# Test.net
KiCad netlist of a schematic drawn in Altium Designer
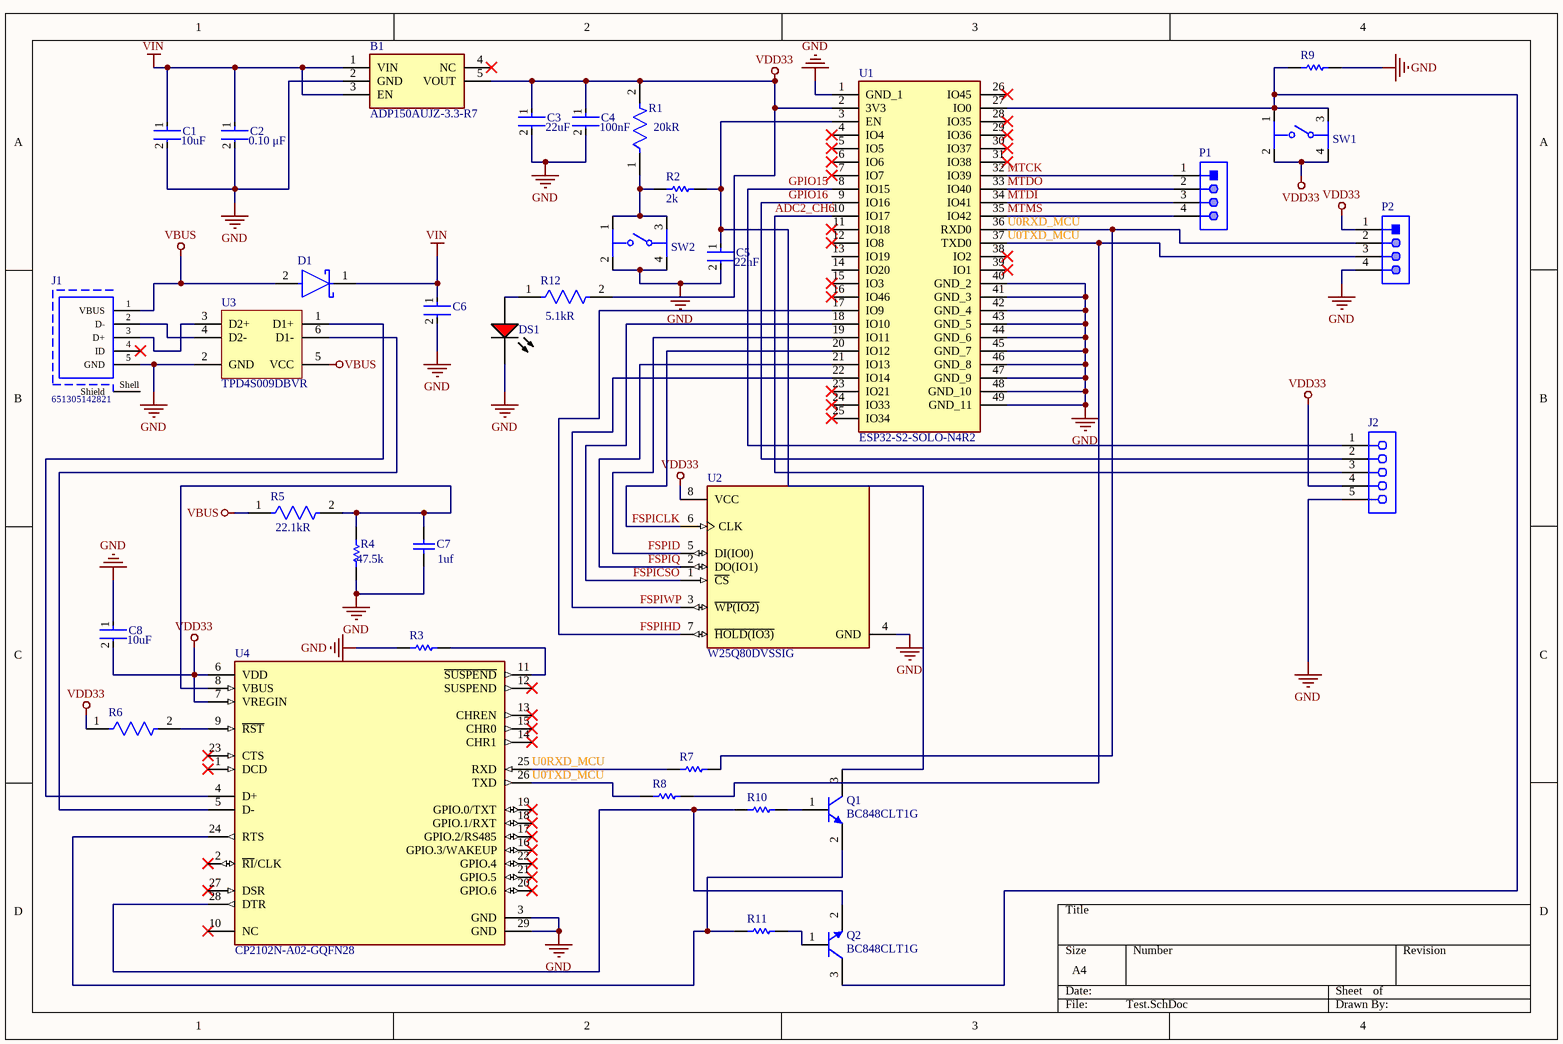
[diagram p0: Test.SchDoc]

(export (version "E")
  (design (tool "Eeschema 10.0.6"))
  (components
    (comp (ref "B1")
      (value "ADP150AUJZ-3.3-R7")
      (footprint "SOT95P280X100-5N")
      (description "Ultralow Noise, 150 mA CMOS Linear Regulator")
      (libsource (lib "Integrated_Library1") (part "ADP150AUJZ-3.3-R7"))
    )
    (comp (ref "C1")
      (value "GRM21BR61C106KE15L")
      (footprint "FP-GRM21B-0_1-IPC_C")
      (description "Chip Multilayer Ceramic Capacitors for General Purpose, 0805, 10uF, X5R, 15%, 10%, 16V")
      (fields
        (field (name "TOLERANCE") "10%")
        (field (name "VOLTAGE") "16V")
        (field (name "CAPACITANCE") "10uF")
      )
      (libsource (lib "Altium Content Vault") (part "b4654b650e69147ec39a6b967a45e02"))
    )
    (comp (ref "C2")
      (value "C1206C104K1RACTU")
      (footprint "FP-C1206C-EB-MFG")
      (description "CAP CER 0.1UF 100V X7R 1206")
      (fields
        (field (name "TOLERANCE") "0.1")
        (field (name "OCTOPART") "https://octopart.com/c1206c104k1ractu-kemet-89521")
        (field (name "CAPACITANCE") "0.10 μF")
      )
      (libsource (lib "Altium Content Vault") (part "b4654b650e69147ec39a6b967a45e02"))
    )
    (comp (ref "C3")
      (value "GRM21BR60J226ME39L")
      (footprint "FP-GRM21B-0_15-MFG")
      (description "Chip Multilayer Ceramic Capacitors for General Purpose, 0805, 22uF, X5R, 15%, 20%, 6.3V")
      (fields
        (field (name "VOLTAGE") "6.3V")
        (field (name "TOLERANCE") "20%")
        (field (name "CAPACITANCE") "22uF")
      )
      (libsource (lib "Altium Content Vault") (part "b4654b650e69147ec39a6b967a45e02"))
    )
    (comp (ref "C4")
      (value "CL03A104KQ3NNNH")
      (footprint "FP-CL03-IPC_B")
      (description "Cap Ceramic 100nF 6.3V X5R ±10% Pad SMD 0201 +85°C T/R")
      (fields (field (name "TOLERANCE") "10%") (field (name "CAPACITANCE") "100nF"))
      (libsource (lib "Altium Content Vault") (part "b4654b650e69147ec39a6b967a45e02"))
    )
    (comp (ref "C5")
      (value "CL21B223KBANNNC")
      (footprint "FP-CL21-IPC_A")
      (description "CL21 Series 0805 22nF 50V ±10% Tolerance X7R Multilayer Ceramic Chip Capacitor")
      (fields
        (field (name "TOLERANCE") "10%")
        (field (name "VOLTAGE") "50V")
        (field (name "CAPACITANCE") "22nF")
      )
      (libsource (lib "Altium Content Vault") (part "b4654b650e69147ec39a6b967a45e02"))
    )
    (comp (ref "C6")
      (value "GRM21BR61E106KA73L")
      (footprint "FP-GRM21B-0_15-IPC_C")
      (description "Chip Multilayer Ceramic Capacitors for General Purpose, 0805, 10uF, X5R, 15%, 10%, 25V")
      (fields (field (name "VOLTAGE") "25V") (field (name "TOLERANCE") "10%"))
      (libsource (lib "Altium Content Vault") (part "b4654b650e69147ec39a6b967a45e02"))
    )
    (comp (ref "C7")
      (value "1uf")
      (footprint "CAPC2013X145X50LL20T25")
      (fields (field (name "MANUFACTURER") "Kemet") (field (name "PART NUMBER") "C0805C105K4PACTU"))
      (libsource (lib "Altium Content Vault") (part "CAP"))
    )
    (comp (ref "C8")
      (value "GRM21BR61C106KE15L")
      (footprint "FP-GRM21B-0_1-IPC_C")
      (description "Chip Multilayer Ceramic Capacitors for General Purpose, 0805, 10uF, X5R, 15%, 10%, 16V")
      (fields
        (field (name "TOLERANCE") "10%")
        (field (name "VOLTAGE") "16V")
        (field (name "CAPACITANCE") "10uF")
      )
      (libsource (lib "Altium Content Vault") (part "b4654b650e69147ec39a6b967a45e02"))
    )
    (comp (ref "D1")
      (value "MSS1P4-M3/89A")
      (footprint "FP-96591-MFG")
      (description "DIODE SCHOTTKY 40V 1A MICROSMP")
      (fields
        (field (name "OCTOPART") "https://octopart.com/mss1p4-m3%2F89a-vishay-42505723")
        (field (name "MANUFACTURER") "Vishay")
      )
      (libsource (lib "Altium Content Vault") (part "c1678fac7984e62e0809fbf79c06691"))
    )
    (comp (ref "DS1")
      (value "TLMS1100-GS08")
      (footprint "VISH-TLMX1100_V")
      (description "LED, RED, 2.1 V, -40 to 100 degC, 2-Pin SMD (0603), RoHS, Tape and Reel")
      (fields (field (name "TOLERANCE") "5%"))
      (libsource (lib "Altium Content Vault") (part "LED-RED-AK-2"))
    )
    (comp (ref "J1")
      (value "651305142821")
      (footprint "651305142821")
      (description "Mini USB 2.0 Type AB Receptacle WR-COM, Horizontal, SMT, with Pads")
      (fields (field (name "MANUFACTURER") "Wurth Elektronik") (field (name "PUBLISHER") "WurthElektronik"))
      (libsource (lib "Altium Content Vault") (part "WE-USB-5-1SHLD"))
    )
    (comp (ref "J2")
      (value "SSW-105-01-G-S")
      (footprint "SMTC-SSW-105-01-X-S")
      (description "SQ Post Socket, Through-hole, Vertical, -55 to 125 degC, 2.54mm Pitch, 5-Pin, Female, RoHS")
      (fields (field (name "MANUFACTURER") "Samtec"))
      (libsource (lib "Altium Content Vault") (part "SMTC-SSW-105-X-X-S"))
    )
    (comp (ref "P1")
      (value "61300411121")
      (footprint "61300411121")
      (description "THT Vertical Pin Header WR-PHD, Pitch 2.54 mm, Single Row, 4 pins")
      (fields (field (name "MANUFACTURER") "Wurth Elektronik") (field (name "PUBLISHER") "WurthElektronik"))
      (libsource (lib "Altium Content Vault") (part "WE-CN-1P-M-R4"))
    )
    (comp (ref "P2")
      (value "61300411121")
      (footprint "61300411121")
      (description "THT Vertical Pin Header WR-PHD, Pitch 2.54 mm, Single Row, 4 pins")
      (fields (field (name "MANUFACTURER") "Wurth Elektronik") (field (name "PUBLISHER") "WurthElektronik"))
      (libsource (lib "Altium Content Vault") (part "WE-CN-1P-M-R4"))
    )
    (comp (ref "Q1")
      (value "BC848CLT1G")
      (footprint "ONSC-SOT-23-3-318-08_V")
      (description "General Purpose Transistor, NPN Silicon, 3-Pin SOT-23, Pb-Free, Tape and Reel")
      (fields (field (name "MANUFACTURER") "On Semiconductor"))
      (libsource (lib "Altium Content Vault") (part "ONSC-NPN-B1E2C3-3"))
    )
    (comp (ref "Q2")
      (value "BC848CLT1G")
      (footprint "ONSC-SOT-23-3-318-08_V")
      (description "General Purpose Transistor, NPN Silicon, 3-Pin SOT-23, Pb-Free, Tape and Reel")
      (fields (field (name "MANUFACTURER") "On Semiconductor"))
      (libsource (lib "Altium Content Vault") (part "ONSC-NPN-B1E2C3-3"))
    )
    (comp (ref "R1")
      (value "AC0603FR-0720KL")
      (footprint "FP-AC0603-MFG")
      (description "RES 20KΩ 1.00% 0.1W 0603")
      (fields (field (name "TOLERANCE") "1%") (field (name "RESISTANCE") "20kR"))
      (libsource (lib "Altium Content Vault") (part "1029c3af85768c4190bb7ad29bc67b5"))
    )
    (comp (ref "R2")
      (value "RC0603FR-072KL")
      (footprint "RESC1608X55X25LL10T15")
      (description "Chip Resistor, 2 KOhm, +/- 1%, 50 V, -55 to 155 degC, 0603 (1608 Metric), RoHS, Tape and Reel")
      (fields
        (field (name "RESISTANCE (OHMS)") "2k")
        (field (name "TOLERANCE") "±1%")
        (field (name "MANUFACTURER") "Yageo")
      )
      (libsource (lib "Altium Content Vault") (part "RES-2"))
    )
    (comp (ref "R3")
      (value "ERJ3EKF1002V")
      (footprint "RESC1609X55X30LL15T15")
      (description "Chip Resistor, 10 KOhm, +/- 1%, 0.1 W, -55 to 155 degC, 0603 (1608 Metric), RoHS, Tape and Reel")
      (fields (field (name "TOLERANCE") "1%") (field (name "MANUFACTURER") "Panasonic"))
      (libsource (lib "Altium Content Vault") (part "RES-2"))
    )
    (comp (ref "R4")
      (value "47.5k")
      (footprint "RESC1609X50X30LL10T20")
      (fields (field (name "MANUFACTURER") "Vishay Dale") (field (name "PART NUMBER") "CRCW060347K5FKEA"))
      (libsource (lib "Altium Content Vault") (part "RES"))
    )
    (comp (ref "R5")
      (value "RC0402FR-0722K1L")
      (footprint "FP-RC0402-0_4-IPC_B")
      (description "RES 22.1K OHM 1% 1/16W 0402")
      (fields (field (name "TOLERANCE") "1%") (field (name "RESISTANCE") "22.1kR"))
      (libsource (lib "Altium Content Vault") (part "1029c3af85768c4190bb7ad29bc67b5"))
    )
    (comp (ref "R6")
      (value "AC0603FR-071KL")
      (footprint "FP-AC0603-MFG")
      (description "RES 1kΩ 1.00% 0.1W 0603")
      (fields (field (name "TOLERANCE") "1%"))
      (libsource (lib "Altium Content Vault") (part "1029c3af85768c4190bb7ad29bc67b5"))
    )
    (comp (ref "R7")
      (value "RC0603JR-070RL")
      (footprint "RESC1608X55X25ML10T15")
      (description "Chip Resistor, 0 Ohm, +/- 5%, 0.1 W, -55 to 155 degC, 0603 (1608 Metric), RoHS, Tape and Reel")
      (fields (field (name "TOLERANCE") "5%") (field (name "MANUFACTURER") "Yageo"))
      (libsource (lib "Altium Content Vault") (part "RES-2"))
    )
    (comp (ref "R8")
      (value "RC0603JR-070RL")
      (footprint "RESC1608X55X25ML10T15")
      (description "Chip Resistor, 0 Ohm, +/- 5%, 0.1 W, -55 to 155 degC, 0603 (1608 Metric), RoHS, Tape and Reel")
      (fields (field (name "TOLERANCE") "5%") (field (name "MANUFACTURER") "Yageo"))
      (libsource (lib "Altium Content Vault") (part "RES-2"))
    )
    (comp (ref "R9")
      (value "ERJ3EKF1002V")
      (footprint "RESC1609X55X30LL15T15")
      (description "Chip Resistor, 10 KOhm, +/- 1%, 0.1 W, -55 to 155 degC, 0603 (1608 Metric), RoHS, Tape and Reel")
      (fields (field (name "TOLERANCE") "1%") (field (name "MANUFACTURER") "Panasonic"))
      (libsource (lib "Altium Content Vault") (part "RES-2"))
    )
    (comp (ref "R10")
      (value "ERJ3EKF1002V")
      (footprint "RESC1609X55X30LL15T15")
      (description "Chip Resistor, 10 KOhm, +/- 1%, 0.1 W, -55 to 155 degC, 0603 (1608 Metric), RoHS, Tape and Reel")
      (fields (field (name "TOLERANCE") "1%") (field (name "MANUFACTURER") "Panasonic"))
      (libsource (lib "Altium Content Vault") (part "RES-2"))
    )
    (comp (ref "R11")
      (value "ERJ3EKF1002V")
      (footprint "RESC1609X55X30LL15T15")
      (description "Chip Resistor, 10 KOhm, +/- 1%, 0.1 W, -55 to 155 degC, 0603 (1608 Metric), RoHS, Tape and Reel")
      (fields (field (name "TOLERANCE") "1%") (field (name "MANUFACTURER") "Panasonic"))
      (libsource (lib "Altium Content Vault") (part "RES-2"))
    )
    (comp (ref "R12")
      (value "CR1206-FX-5101ELF")
      (footprint "FP-CR1206-IPC_B")
      (description "Thick Film Chip Resistors 1206 5.1kΩ 0.25W 1% 100ppm/°C")
      (fields (field (name "TOLERANCE") "1%") (field (name "RESISTANCE") "5.1kR"))
      (libsource (lib "Altium Content Vault") (part "1029c3af85768c4190bb7ad29bc67b5"))
    )
    (comp (ref "SW1")
      (value "PTS810 SJG 250 SMTR LFS")
      (footprint "FP-PTS810_SJG_250_SMTR_LF-MFG")
      (description "SWITCH TACTILE SPST-NO 0.05A 16V")
      (fields
        (field (name "MANUFACTURER") "C&K Components")
        (field (name "OCTOPART") "https://octopart.com/pts810sjg250smtrlfs-c%26k+components-29380277")
      )
      (libsource (lib "Altium Content Vault") (part "1adf0dd01260c80cf25a44bfd6b99ba"))
    )
    (comp (ref "SW2")
      (value "PTS810 SJG 250 SMTR LFS")
      (footprint "FP-PTS810_SJG_250_SMTR_LF-MFG")
      (description "SWITCH TACTILE SPST-NO 0.05A 16V")
      (fields
        (field (name "MANUFACTURER") "C&K Components")
        (field (name "OCTOPART") "https://octopart.com/pts810sjg250smtrlfs-c%26k+components-29380277")
      )
      (libsource (lib "Altium Content Vault") (part "1adf0dd01260c80cf25a44bfd6b99ba"))
    )
    (comp (ref "U1")
      (value "ESP32-S2-SOLO-N4R2")
      (footprint "ESP32S2SOLON4R2")
      (fields (field (name "MOUSER PART NUMBER") "356-ESP32-S2SOLON4R2"))
      (libsource (lib "Integrated_Library1") (part "ESP32-S2-SOLO-N4R2"))
    )
    (comp (ref "U2")
      (value "W25Q80DVSSIG")
      (footprint "FP-SS-MFG")
      (description "IC FLASH 8MBIT SPI 104MHZ 8SOIC")
      (libsource (lib "Altium Content Vault") (part "04025d3425be9a6c88c6bb112b73860"))
    )
    (comp (ref "U3")
      (value "TPD4S009DBVR")
      (footprint "DBV0006A_L")
      (fields (field (name "MANUFACTURER") "Texas Instruments"))
      (libsource (lib "Altium Content Vault") (part "TI-TPD4S009-SOT-23_DBV-6"))
    )
    (comp (ref "U4")
      (value "CP2102N-A02-GQFN28")
      (footprint "FP-CP2102N-A02-GQFN28-MFG")
      (description "IC USB TO UART BRIDGE QFN28")
      (libsource (lib "Altium Content Vault") (part "f8fb43f618a03b32512863a7a8093b6"))
    )
  )
  (nets
    (net (code "1") (name "/ADC2_CH6") (class "Default")
      (node (ref "J2") (pin "3") (pinfunction "3_3") (pintype "passive"))
      (node (ref "U1") (pin "10") (pinfunction "IO17_10") (pintype "passive"))
    )
    (net (code "2") (name "/FSPICLK") (class "Default")
      (node (ref "U1") (pin "20") (pinfunction "IO12_20") (pintype "passive"))
      (node (ref "U2") (pin "6") (pinfunction "CLK_6") (pintype "input"))
    )
    (net (code "3") (name "/FSPICSO") (class "Default")
      (node (ref "U1") (pin "18") (pinfunction "IO10_18") (pintype "passive"))
      (node (ref "U2") (pin "1") (pinfunction "~{CS}_1") (pintype "input"))
    )
    (net (code "4") (name "/FSPID") (class "Default")
      (node (ref "U1") (pin "19") (pinfunction "IO11_19") (pintype "passive"))
      (node (ref "U2") (pin "5") (pinfunction "DI(IO0)_5") (pintype "bidirectional"))
    )
    (net (code "5") (name "/FSPIHD") (class "Default")
      (node (ref "U1") (pin "17") (pinfunction "IO9_17") (pintype "passive"))
      (node (ref "U2") (pin "7") (pinfunction "~{HOLD(IO3)}_7") (pintype "bidirectional"))
    )
    (net (code "6") (name "/FSPIQ") (class "Default")
      (node (ref "U1") (pin "21") (pinfunction "IO13_21") (pintype "passive"))
      (node (ref "U2") (pin "2") (pinfunction "DO(IO1)_2") (pintype "bidirectional"))
    )
    (net (code "7") (name "/FSPIWP") (class "Default")
      (node (ref "U1") (pin "22") (pinfunction "IO14_22") (pintype "passive"))
      (node (ref "U2") (pin "3") (pinfunction "~{WP(IO2)}_3") (pintype "bidirectional"))
    )
    (net (code "8") (name "/GPIO15") (class "Default")
      (node (ref "J2") (pin "1") (pinfunction "1_1") (pintype "passive"))
      (node (ref "U1") (pin "8") (pinfunction "IO15_8") (pintype "passive"))
    )
    (net (code "9") (name "/GPIO16") (class "Default")
      (node (ref "J2") (pin "2") (pinfunction "2_2") (pintype "passive"))
      (node (ref "U1") (pin "9") (pinfunction "IO16_9") (pintype "passive"))
    )
    (net (code "10") (name "/MTCK") (class "Default")
      (node (ref "P1") (pin "1") (pinfunction "1_1") (pintype "passive"))
      (node (ref "U1") (pin "32") (pinfunction "IO39_32") (pintype "passive"))
    )
    (net (code "11") (name "/MTDI") (class "Default")
      (node (ref "P1") (pin "3") (pinfunction "3_3") (pintype "passive"))
      (node (ref "U1") (pin "34") (pinfunction "IO41_34") (pintype "passive"))
    )
    (net (code "12") (name "/MTDO") (class "Default")
      (node (ref "P1") (pin "2") (pinfunction "2_2") (pintype "passive"))
      (node (ref "U1") (pin "33") (pinfunction "IO40_33") (pintype "passive"))
    )
    (net (code "13") (name "/MTMS") (class "Default")
      (node (ref "P1") (pin "4") (pinfunction "4_4") (pintype "passive"))
      (node (ref "U1") (pin "35") (pinfunction "IO42_35") (pintype "passive"))
    )
    (net (code "14") (name "/U0RXD_MCU") (class "Default")
      (node (ref "P2") (pin "2") (pinfunction "2_2") (pintype "passive"))
      (node (ref "R7") (pin "1") (pinfunction "1_1") (pintype "passive"))
      (node (ref "R7") (pin "2") (pinfunction "2_2") (pintype "passive"))
      (node (ref "U1") (pin "36") (pinfunction "RXD0_36") (pintype "passive"))
      (node (ref "U4") (pin "25") (pinfunction "RXD_25") (pintype "input"))
    )
    (net (code "15") (name "/U0TXD_MCU") (class "Default")
      (node (ref "P2") (pin "3") (pinfunction "3_3") (pintype "passive"))
      (node (ref "R8") (pin "1") (pinfunction "1_1") (pintype "passive"))
      (node (ref "R8") (pin "2") (pinfunction "2_2") (pintype "passive"))
      (node (ref "U1") (pin "37") (pinfunction "TXD0_37") (pintype "passive"))
      (node (ref "U4") (pin "26") (pinfunction "TXD_26") (pintype "output"))
    )
    (net (code "16") (name "GND") (class "Default")
      (node (ref "B1") (pin "2") (pinfunction "GND_2") (pintype "passive"))
      (node (ref "C1") (pin "2") (pinfunction "2_2") (pintype "passive"))
      (node (ref "C2") (pin "2") (pinfunction "2_2") (pintype "passive"))
      (node (ref "C3") (pin "2") (pinfunction "2_2") (pintype "passive"))
      (node (ref "C4") (pin "2") (pinfunction "2_2") (pintype "passive"))
      (node (ref "C5") (pin "2") (pinfunction "2_2") (pintype "passive"))
      (node (ref "C6") (pin "2") (pinfunction "2_2") (pintype "passive"))
      (node (ref "C7") (pin "1") (pinfunction "1_1") (pintype "passive"))
      (node (ref "C8") (pin "1") (pinfunction "1_1") (pintype "passive"))
      (node (ref "DS1") (pin "2") (pinfunction "K_2") (pintype "passive"))
      (node (ref "J1") (pin "5") (pinfunction "GND_5") (pintype "passive"))
      (node (ref "J2") (pin "5") (pinfunction "5_5") (pintype "passive"))
      (node (ref "P2") (pin "4") (pinfunction "4_4") (pintype "passive"))
      (node (ref "R3") (pin "1") (pinfunction "1_1") (pintype "passive"))
      (node (ref "R4") (pin "1") (pinfunction "1_1") (pintype "passive"))
      (node (ref "R9") (pin "2") (pinfunction "2_2") (pintype "passive"))
      (node (ref "SW2") (pin "2") (pinfunction "2_2") (pintype "passive"))
      (node (ref "SW2") (pin "4") (pinfunction "4_4") (pintype "passive"))
      (node (ref "U1") (pin "1") (pinfunction "GND_1_1") (pintype "passive"))
      (node (ref "U1") (pin "40") (pinfunction "GND_2_40") (pintype "passive"))
      (node (ref "U1") (pin "41") (pinfunction "GND_3_41") (pintype "passive"))
      (node (ref "U1") (pin "42") (pinfunction "GND_4_42") (pintype "passive"))
      (node (ref "U1") (pin "43") (pinfunction "GND_5_43") (pintype "passive"))
      (node (ref "U1") (pin "44") (pinfunction "GND_6_44") (pintype "passive"))
      (node (ref "U1") (pin "45") (pinfunction "GND_7_45") (pintype "passive"))
      (node (ref "U1") (pin "46") (pinfunction "GND_8_46") (pintype "passive"))
      (node (ref "U1") (pin "47") (pinfunction "GND_9_47") (pintype "passive"))
      (node (ref "U1") (pin "48") (pinfunction "GND_10_48") (pintype "passive"))
      (node (ref "U1") (pin "49") (pinfunction "GND_11_49") (pintype "passive"))
      (node (ref "U2") (pin "4") (pinfunction "GND_4") (pintype "power_in"))
      (node (ref "U3") (pin "2") (pinfunction "GND_2") (pintype "power_in"))
      (node (ref "U4") (pin "29") (pinfunction "GND_29") (pintype "power_in"))
      (node (ref "U4") (pin "3") (pinfunction "GND_3") (pintype "power_in"))
    )
    (net (code "17") (name "Net-(DS1-A)") (class "Default")
      (node (ref "DS1") (pin "1") (pinfunction "A_1") (pintype "passive"))
      (node (ref "R12") (pin "1") (pinfunction "1_1") (pintype "passive"))
    )
    (net (code "18") (name "Net-(J1-D+)") (class "Default")
      (node (ref "J1") (pin "3") (pinfunction "D+_3") (pintype "passive"))
      (node (ref "U3") (pin "3") (pinfunction "D2+_3") (pintype "passive"))
    )
    (net (code "19") (name "Net-(J1-D-)") (class "Default")
      (node (ref "J1") (pin "2") (pinfunction "D-_2") (pintype "passive"))
      (node (ref "U3") (pin "4") (pinfunction "D2-_4") (pintype "passive"))
    )
    (net (code "20") (name "Net-(Q1-B)") (class "Default")
      (node (ref "Q1") (pin "1") (pinfunction "B_1") (pintype "passive"))
      (node (ref "R10") (pin "2") (pinfunction "2_2") (pintype "passive"))
    )
    (net (code "21") (name "Net-(Q1-C)") (class "Default")
      (node (ref "C5") (pin "1") (pinfunction "1_1") (pintype "passive"))
      (node (ref "Q1") (pin "3") (pinfunction "C_3") (pintype "passive"))
      (node (ref "R2") (pin "1") (pinfunction "1_1") (pintype "passive"))
      (node (ref "U1") (pin "3") (pinfunction "EN_3") (pintype "passive"))
    )
    (net (code "22") (name "Net-(Q1-E)") (class "Default")
      (node (ref "Q1") (pin "2") (pinfunction "E_2") (pintype "passive"))
      (node (ref "R11") (pin "1") (pinfunction "1_1") (pintype "passive"))
      (node (ref "U4") (pin "24") (pinfunction "RTS_24") (pintype "output"))
    )
    (net (code "23") (name "Net-(Q2-B)") (class "Default")
      (node (ref "Q2") (pin "1") (pinfunction "B_1") (pintype "passive"))
      (node (ref "R11") (pin "2") (pinfunction "2_2") (pintype "passive"))
    )
    (net (code "24") (name "Net-(Q2-C)") (class "Default")
      (node (ref "Q2") (pin "3") (pinfunction "C_3") (pintype "passive"))
      (node (ref "R9") (pin "1") (pinfunction "1_1") (pintype "passive"))
      (node (ref "SW1") (pin "1") (pinfunction "1_1") (pintype "passive"))
      (node (ref "SW1") (pin "3") (pinfunction "3_3") (pintype "passive"))
      (node (ref "U1") (pin "27") (pinfunction "IO0_27") (pintype "passive"))
    )
    (net (code "25") (name "Net-(Q2-E)") (class "Default")
      (node (ref "Q2") (pin "2") (pinfunction "E_2") (pintype "passive"))
      (node (ref "R10") (pin "1") (pinfunction "1_1") (pintype "passive"))
      (node (ref "U4") (pin "28") (pinfunction "DTR_28") (pintype "output"))
    )
    (net (code "26") (name "Net-(R1-Pad1)") (class "Default")
      (node (ref "R1") (pin "1") (pinfunction "1_1") (pintype "passive"))
      (node (ref "R2") (pin "2") (pinfunction "2_2") (pintype "passive"))
      (node (ref "SW2") (pin "1") (pinfunction "1_1") (pintype "passive"))
      (node (ref "SW2") (pin "3") (pinfunction "3_3") (pintype "passive"))
    )
    (net (code "27") (name "Net-(U3-D1+)") (class "Default")
      (node (ref "U3") (pin "1") (pinfunction "D1+_1") (pintype "passive"))
      (node (ref "U4") (pin "4") (pinfunction "D+_4") (pintype "passive"))
    )
    (net (code "28") (name "Net-(U3-D1-)") (class "Default")
      (node (ref "U3") (pin "6") (pinfunction "D1-_6") (pintype "passive"))
      (node (ref "U4") (pin "5") (pinfunction "D-_5") (pintype "passive"))
    )
    (net (code "29") (name "Net-(U4-VBUS)") (class "Default")
      (node (ref "C7") (pin "2") (pinfunction "2_2") (pintype "passive"))
      (node (ref "R4") (pin "2") (pinfunction "2_2") (pintype "passive"))
      (node (ref "R5") (pin "2") (pinfunction "2_2") (pintype "passive"))
      (node (ref "U4") (pin "8") (pinfunction "VBUS_8") (pintype "input"))
    )
    (net (code "30") (name "Net-(U4-~{RST})") (class "Default")
      (node (ref "R6") (pin "2") (pinfunction "2_2") (pintype "passive"))
      (node (ref "U4") (pin "9") (pinfunction "~{RST}_9") (pintype "input"))
    )
    (net (code "31") (name "Net-(U4-~{SUSPEND})") (class "Default")
      (node (ref "R3") (pin "2") (pinfunction "2_2") (pintype "passive"))
      (node (ref "U4") (pin "11") (pinfunction "~{SUSPEND}_11") (pintype "output"))
    )
    (net (code "32") (name "VBUS") (class "Default")
      (node (ref "D1") (pin "2") (pinfunction "A_2") (pintype "passive"))
      (node (ref "J1") (pin "1") (pinfunction "VBUS_1") (pintype "passive"))
      (node (ref "R5") (pin "1") (pinfunction "1_1") (pintype "passive"))
      (node (ref "U3") (pin "5") (pinfunction "VCC_5") (pintype "power_in"))
    )
    (net (code "33") (name "VDD33") (class "Default")
      (node (ref "B1") (pin "5") (pinfunction "VOUT_5") (pintype "passive"))
      (node (ref "C3") (pin "1") (pinfunction "1_1") (pintype "passive"))
      (node (ref "C4") (pin "1") (pinfunction "1_1") (pintype "passive"))
      (node (ref "C8") (pin "2") (pinfunction "2_2") (pintype "passive"))
      (node (ref "J2") (pin "4") (pinfunction "4_4") (pintype "passive"))
      (node (ref "P2") (pin "1") (pinfunction "1_1") (pintype "passive"))
      (node (ref "R1") (pin "2") (pinfunction "2_2") (pintype "passive"))
      (node (ref "R12") (pin "2") (pinfunction "2_2") (pintype "passive"))
      (node (ref "R6") (pin "1") (pinfunction "1_1") (pintype "passive"))
      (node (ref "SW1") (pin "2") (pinfunction "2_2") (pintype "passive"))
      (node (ref "SW1") (pin "4") (pinfunction "4_4") (pintype "passive"))
      (node (ref "U1") (pin "2") (pinfunction "3V3_2") (pintype "passive"))
      (node (ref "U2") (pin "8") (pinfunction "VCC_8") (pintype "power_in"))
      (node (ref "U4") (pin "6") (pinfunction "VDD_6") (pintype "power_in"))
      (node (ref "U4") (pin "7") (pinfunction "VREGIN_7") (pintype "input"))
    )
    (net (code "34") (name "VIN") (class "Default")
      (node (ref "B1") (pin "1") (pinfunction "VIN_1") (pintype "passive"))
      (node (ref "B1") (pin "3") (pinfunction "EN_3") (pintype "passive"))
      (node (ref "C1") (pin "1") (pinfunction "1_1") (pintype "passive"))
      (node (ref "C2") (pin "1") (pinfunction "1_1") (pintype "passive"))
      (node (ref "C6") (pin "1") (pinfunction "1_1") (pintype "passive"))
      (node (ref "D1") (pin "1") (pinfunction "C_1") (pintype "passive"))
    )
    (net (code "35") (name "unconnected-(B1-NC-Pad4)") (class "Default")
      (node (ref "B1") (pin "4") (pinfunction "NC_4") (pintype "passive+no_connect"))
    )
    (net (code "36") (name "unconnected-(J1-ID-Pad4)") (class "Default")
      (node (ref "J1") (pin "4") (pinfunction "ID_4") (pintype "passive+no_connect"))
    )
    (net (code "37") (name "unconnected-(J1-Shield-PadShell)") (class "Default")
      (node (ref "J1") (pin "Shell") (pinfunction "Shield_Shell") (pintype "passive"))
    )
    (net (code "38") (name "unconnected-(U1-IO1-Pad39)") (class "Default")
      (node (ref "U1") (pin "39") (pinfunction "IO1_39") (pintype "passive+no_connect"))
    )
    (net (code "39") (name "unconnected-(U1-IO2-Pad38)") (class "Default")
      (node (ref "U1") (pin "38") (pinfunction "IO2_38") (pintype "passive+no_connect"))
    )
    (net (code "40") (name "unconnected-(U1-IO3-Pad15)") (class "Default")
      (node (ref "U1") (pin "15") (pinfunction "IO3_15") (pintype "passive+no_connect"))
    )
    (net (code "41") (name "unconnected-(U1-IO4-Pad4)") (class "Default")
      (node (ref "U1") (pin "4") (pinfunction "IO4_4") (pintype "passive+no_connect"))
    )
    (net (code "42") (name "unconnected-(U1-IO5-Pad5)") (class "Default")
      (node (ref "U1") (pin "5") (pinfunction "IO5_5") (pintype "passive+no_connect"))
    )
    (net (code "43") (name "unconnected-(U1-IO6-Pad6)") (class "Default")
      (node (ref "U1") (pin "6") (pinfunction "IO6_6") (pintype "passive+no_connect"))
    )
    (net (code "44") (name "unconnected-(U1-IO7-Pad7)") (class "Default")
      (node (ref "U1") (pin "7") (pinfunction "IO7_7") (pintype "passive+no_connect"))
    )
    (net (code "45") (name "unconnected-(U1-IO8-Pad12)") (class "Default")
      (node (ref "U1") (pin "12") (pinfunction "IO8_12") (pintype "passive+no_connect"))
    )
    (net (code "46") (name "unconnected-(U1-IO18-Pad11)") (class "Default")
      (node (ref "U1") (pin "11") (pinfunction "IO18_11") (pintype "passive+no_connect"))
    )
    (net (code "47") (name "unconnected-(U1-IO19-Pad13)") (class "Default")
      (node (ref "U1") (pin "13") (pinfunction "IO19_13") (pintype "passive"))
    )
    (net (code "48") (name "unconnected-(U1-IO20-Pad14)") (class "Default")
      (node (ref "U1") (pin "14") (pinfunction "IO20_14") (pintype "passive"))
    )
    (net (code "49") (name "unconnected-(U1-IO21-Pad23)") (class "Default")
      (node (ref "U1") (pin "23") (pinfunction "IO21_23") (pintype "passive+no_connect"))
    )
    (net (code "50") (name "unconnected-(U1-IO33-Pad24)") (class "Default")
      (node (ref "U1") (pin "24") (pinfunction "IO33_24") (pintype "passive+no_connect"))
    )
    (net (code "51") (name "unconnected-(U1-IO34-Pad25)") (class "Default")
      (node (ref "U1") (pin "25") (pinfunction "IO34_25") (pintype "passive+no_connect"))
    )
    (net (code "52") (name "unconnected-(U1-IO35-Pad28)") (class "Default")
      (node (ref "U1") (pin "28") (pinfunction "IO35_28") (pintype "passive+no_connect"))
    )
    (net (code "53") (name "unconnected-(U1-IO36-Pad29)") (class "Default")
      (node (ref "U1") (pin "29") (pinfunction "IO36_29") (pintype "passive+no_connect"))
    )
    (net (code "54") (name "unconnected-(U1-IO37-Pad30)") (class "Default")
      (node (ref "U1") (pin "30") (pinfunction "IO37_30") (pintype "passive+no_connect"))
    )
    (net (code "55") (name "unconnected-(U1-IO38-Pad31)") (class "Default")
      (node (ref "U1") (pin "31") (pinfunction "IO38_31") (pintype "passive+no_connect"))
    )
    (net (code "56") (name "unconnected-(U1-IO45-Pad26)") (class "Default")
      (node (ref "U1") (pin "26") (pinfunction "IO45_26") (pintype "passive+no_connect"))
    )
    (net (code "57") (name "unconnected-(U1-IO46-Pad16)") (class "Default")
      (node (ref "U1") (pin "16") (pinfunction "IO46_16") (pintype "passive+no_connect"))
    )
    (net (code "58") (name "unconnected-(U4-CHR0-Pad15)") (class "Default")
      (node (ref "U4") (pin "15") (pinfunction "CHR0_15") (pintype "output+no_connect"))
    )
    (net (code "59") (name "unconnected-(U4-CHR1-Pad14)") (class "Default")
      (node (ref "U4") (pin "14") (pinfunction "CHR1_14") (pintype "output+no_connect"))
    )
    (net (code "60") (name "unconnected-(U4-CHREN-Pad13)") (class "Default")
      (node (ref "U4") (pin "13") (pinfunction "CHREN_13") (pintype "output+no_connect"))
    )
    (net (code "61") (name "unconnected-(U4-CTS-Pad23)") (class "Default")
      (node (ref "U4") (pin "23") (pinfunction "CTS_23") (pintype "input+no_connect"))
    )
    (net (code "62") (name "unconnected-(U4-DCD-Pad1)") (class "Default")
      (node (ref "U4") (pin "1") (pinfunction "DCD_1") (pintype "input+no_connect"))
    )
    (net (code "63") (name "unconnected-(U4-DSR-Pad27)") (class "Default")
      (node (ref "U4") (pin "27") (pinfunction "DSR_27") (pintype "input+no_connect"))
    )
    (net (code "64") (name "unconnected-(U4-GPIO.0{slash}TXT-Pad19)") (class "Default")
      (node (ref "U4") (pin "19") (pinfunction "GPIO.0/TXT_19") (pintype "bidirectional+no_connect"))
    )
    (net (code "65") (name "unconnected-(U4-GPIO.1{slash}RXT-Pad18)") (class "Default")
      (node (ref "U4") (pin "18") (pinfunction "GPIO.1/RXT_18") (pintype "bidirectional+no_connect"))
    )
    (net (code "66") (name "unconnected-(U4-GPIO.2{slash}RS485-Pad17)") (class "Default")
      (node (ref "U4") (pin "17") (pinfunction "GPIO.2/RS485_17") (pintype "bidirectional+no_connect"))
    )
    (net (code "67") (name "unconnected-(U4-GPIO.3{slash}WAKEUP-Pad16)") (class "Default")
      (node (ref "U4") (pin "16") (pinfunction "GPIO.3/WAKEUP_16") (pintype "bidirectional+no_connect"))
    )
    (net (code "68") (name "unconnected-(U4-GPIO.4-Pad22)") (class "Default")
      (node (ref "U4") (pin "22") (pinfunction "GPIO.4_22") (pintype "bidirectional+no_connect"))
    )
    (net (code "69") (name "unconnected-(U4-GPIO.5-Pad21)") (class "Default")
      (node (ref "U4") (pin "21") (pinfunction "GPIO.5_21") (pintype "bidirectional+no_connect"))
    )
    (net (code "70") (name "unconnected-(U4-GPIO.6-Pad20)") (class "Default")
      (node (ref "U4") (pin "20") (pinfunction "GPIO.6_20") (pintype "bidirectional+no_connect"))
    )
    (net (code "71") (name "unconnected-(U4-NC-Pad10)") (class "Default")
      (node (ref "U4") (pin "10") (pinfunction "NC_10") (pintype "passive+no_connect"))
    )
    (net (code "72") (name "unconnected-(U4-SUSPEND-Pad12)") (class "Default")
      (node (ref "U4") (pin "12") (pinfunction "SUSPEND_12") (pintype "output+no_connect"))
    )
    (net (code "73") (name "unconnected-(U4-~{RI}{slash}CLK-Pad2)") (class "Default")
      (node (ref "U4") (pin "2") (pinfunction "~{RI}/CLK_2") (pintype "bidirectional+no_connect"))
    )
  )
)
